# Power.net
KiCad netlist of a schematic drawn in Altium Designer
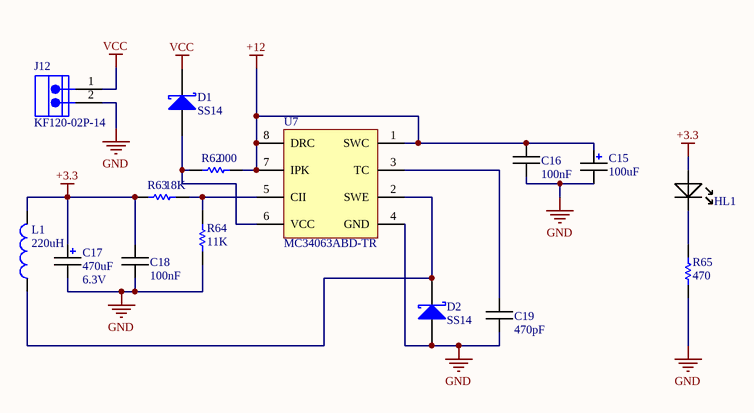
[diagram p0: Power.SchDoc]

(export (version "E")
  (design (tool "Eeschema 10.0.6"))
  (components
    (comp (ref "C15")
      (value "CAP_ELEC_SMD")
      (footprint "ECAP_SMD_6.3mmx5.4mm")
      (fields (field (name "VAL") "100uF"))
      (libsource (lib "altium-import") (part "root_3_CAP_ELEC_SMD_"))
    )
    (comp (ref "C16")
      (value "CAP_SMD")
      (footprint "CAP0805")
      (description "Ceramic capacitor, 0805")
      (fields (field (name "VAL") "100nF"))
      (libsource (lib "altium-import") (part "root_1_CAP_SMD_"))
    )
    (comp (ref "C17")
      (value "CAP_ELEC_SMD")
      (footprint "ECAP_SMD_8mmx10mm")
      (fields (field (name "RATED CAPACITANCE") "470uF") (field (name "RATED VOLTAGE") "6.3V"))
      (libsource (lib "altium-import") (part "root_3_CAP_ELEC_SMD_"))
    )
    (comp (ref "C18")
      (value "CAP_SMD")
      (footprint "CAPC1206(3216)170_L")
      (description "Ceramic capacitor, 0805")
      (fields (field (name "VAL") "100nF"))
      (libsource (lib "altium-import") (part "root_1_CAP_SMD_"))
    )
    (comp (ref "C19")
      (value "CAP_SMD")
      (footprint "CAPC1206(3216)170_L")
      (description "Ceramic capacitor, 0805")
      (fields (field (name "VAL") "470pF"))
      (libsource (lib "altium-import") (part "root_1_CAP_SMD_"))
    )
    (comp (ref "D1")
      (value "SS14")
      (footprint "DO-214")
      (description "Schottky Rectifier, 1.1 W, -65 to 125 degC, 2-Pin SMD, RoHS, Tape and Reel")
      (fields (field (name "MANUFACTURER") "Fairchild"))
      (libsource (lib "altium-import") (part "root_1_SS14_"))
    )
    (comp (ref "D2")
      (value "SS14")
      (footprint "DO-214")
      (description "Schottky Rectifier, 1.1 W, -65 to 125 degC, 2-Pin SMD, RoHS, Tape and Reel")
      (fields (field (name "MANUFACTURER") "Fairchild"))
      (libsource (lib "altium-import") (part "root_1_SS14_"))
    )
    (comp (ref "HL1")
      (value "LED_SMD")
      (footprint "0805_LED")
      (description "0805 led")
      (libsource (lib "altium-import") (part "root_3_LED_SMD_"))
    )
    (comp (ref "J12")
      (value "KF120-02P-14")
      (footprint "DG301-5.0-02P-1X")
      (fields (field (name "MANUFACTURER") "Cixi KaiFeng") (field (name "CONTACT") "Brass"))
      (libsource (lib "altium-import") (part "root_3_mirrored_Terminal_2_"))
    )
    (comp (ref "L1")
      (value "220uH")
      (footprint "SDR1006_SMD")
      (description "Inductor for Power Circuits")
      (fields (field (name "TOLERANCE") "±30%") (field (name "MANUFACTURER") "TDK"))
      (libsource (lib "web.skorpio") (part "Inductor power"))
    )
    (comp (ref "R62")
      (value "RES_SMD")
      (footprint "RES0805")
      (fields (field (name "VAL") "000"))
      (libsource (lib "altium-import") (part "root_0_RES_SMD_"))
    )
    (comp (ref "R63")
      (value "RES_SMD")
      (footprint "RES0805")
      (fields (field (name "VAL") "18K"))
      (libsource (lib "altium-import") (part "root_0_RES_SMD_"))
    )
    (comp (ref "R64")
      (value "RES_SMD")
      (footprint "RES0805")
      (fields (field (name "VAL") "11K"))
      (libsource (lib "altium-import") (part "root_1_RES_SMD_"))
    )
    (comp (ref "R65")
      (value "RES_SMD")
      (footprint "RES0805")
      (fields (field (name "VAL") "470"))
      (libsource (lib "altium-import") (part "root_1_RES_SMD_"))
    )
    (comp (ref "U7")
      (value "MC34063ABD-TR")
      (footprint "SO-8_M")
      (description "DC/DC converter control circuit, 8-Pin SO, Tape and Reel")
      (libsource (lib "altium-import") (part "root_0_MC34063A_"))
    )
  )
  (nets
    (net (code "1") (name "+3.3") (class "Default")
      (node (ref "C17") (pin "1") (pinfunction "1_1") (pintype "passive"))
      (node (ref "C18") (pin "2") (pinfunction "2_2") (pintype "passive"))
      (node (ref "HL1") (pin "1") (pinfunction "anode_1") (pintype "passive"))
      (node (ref "L1") (pin "2") (pinfunction "2_2") (pintype "passive"))
      (node (ref "R63") (pin "1") (pinfunction "1_1") (pintype "passive"))
    )
    (net (code "2") (name "+12") (class "Default")
      (node (ref "C15") (pin "1") (pinfunction "1_1") (pintype "passive"))
      (node (ref "C16") (pin "2") (pinfunction "2_2") (pintype "passive"))
      (node (ref "R62") (pin "2") (pinfunction "2_2") (pintype "passive"))
      (node (ref "U7") (pin "1") (pinfunction "SWC_1") (pintype "open_collector"))
      (node (ref "U7") (pin "7") (pinfunction "IPK_7") (pintype "passive"))
      (node (ref "U7") (pin "8") (pinfunction "DRC_8") (pintype "open_collector"))
    )
    (net (code "3") (name "GND") (class "Default")
      (node (ref "C15") (pin "2") (pinfunction "2_2") (pintype "passive"))
      (node (ref "C16") (pin "1") (pinfunction "1_1") (pintype "passive"))
      (node (ref "C17") (pin "2") (pinfunction "2_2") (pintype "passive"))
      (node (ref "C18") (pin "1") (pinfunction "1_1") (pintype "passive"))
      (node (ref "C19") (pin "1") (pinfunction "1_1") (pintype "passive"))
      (node (ref "D2") (pin "2") (pinfunction "A_2") (pintype "passive"))
      (node (ref "J12") (pin "2") (pinfunction "2_2") (pintype "passive"))
      (node (ref "R64") (pin "1") (pinfunction "1_1") (pintype "passive"))
      (node (ref "R65") (pin "1") (pinfunction "1_1") (pintype "passive"))
      (node (ref "U7") (pin "4") (pinfunction "GND_4") (pintype "power_in"))
    )
    (net (code "4") (name "Net-(D1-A)") (class "Default")
      (node (ref "D1") (pin "2") (pinfunction "A_2") (pintype "passive"))
      (node (ref "R62") (pin "1") (pinfunction "1_1") (pintype "passive"))
      (node (ref "U7") (pin "6") (pinfunction "VCC_6") (pintype "power_in"))
    )
    (net (code "5") (name "Net-(D2-K)") (class "Default")
      (node (ref "D2") (pin "1") (pinfunction "K_1") (pintype "passive"))
      (node (ref "L1") (pin "1") (pinfunction "1_1") (pintype "passive"))
      (node (ref "U7") (pin "2") (pinfunction "SWE_2") (pintype "open_emitter"))
    )
    (net (code "6") (name "Net-(HL1-cathode)") (class "Default")
      (node (ref "HL1") (pin "2") (pinfunction "cathode_2") (pintype "passive"))
      (node (ref "R65") (pin "2") (pinfunction "2_2") (pintype "passive"))
    )
    (net (code "7") (name "Net-(U7-CII)") (class "Default")
      (node (ref "R63") (pin "2") (pinfunction "2_2") (pintype "passive"))
      (node (ref "R64") (pin "2") (pinfunction "2_2") (pintype "passive"))
      (node (ref "U7") (pin "5") (pinfunction "CII_5") (pintype "passive"))
    )
    (net (code "8") (name "Net-(U7-TC)") (class "Default")
      (node (ref "C19") (pin "2") (pinfunction "2_2") (pintype "passive"))
      (node (ref "U7") (pin "3") (pinfunction "TC_3") (pintype "passive"))
    )
    (net (code "9") (name "VCC") (class "Default")
      (node (ref "D1") (pin "1") (pinfunction "K_1") (pintype "passive"))
      (node (ref "J12") (pin "1") (pinfunction "1_1") (pintype "passive"))
    )
  )
)
